# RWcircuit_1.net
KiCad netlist of a schematic drawn in Altium Designer
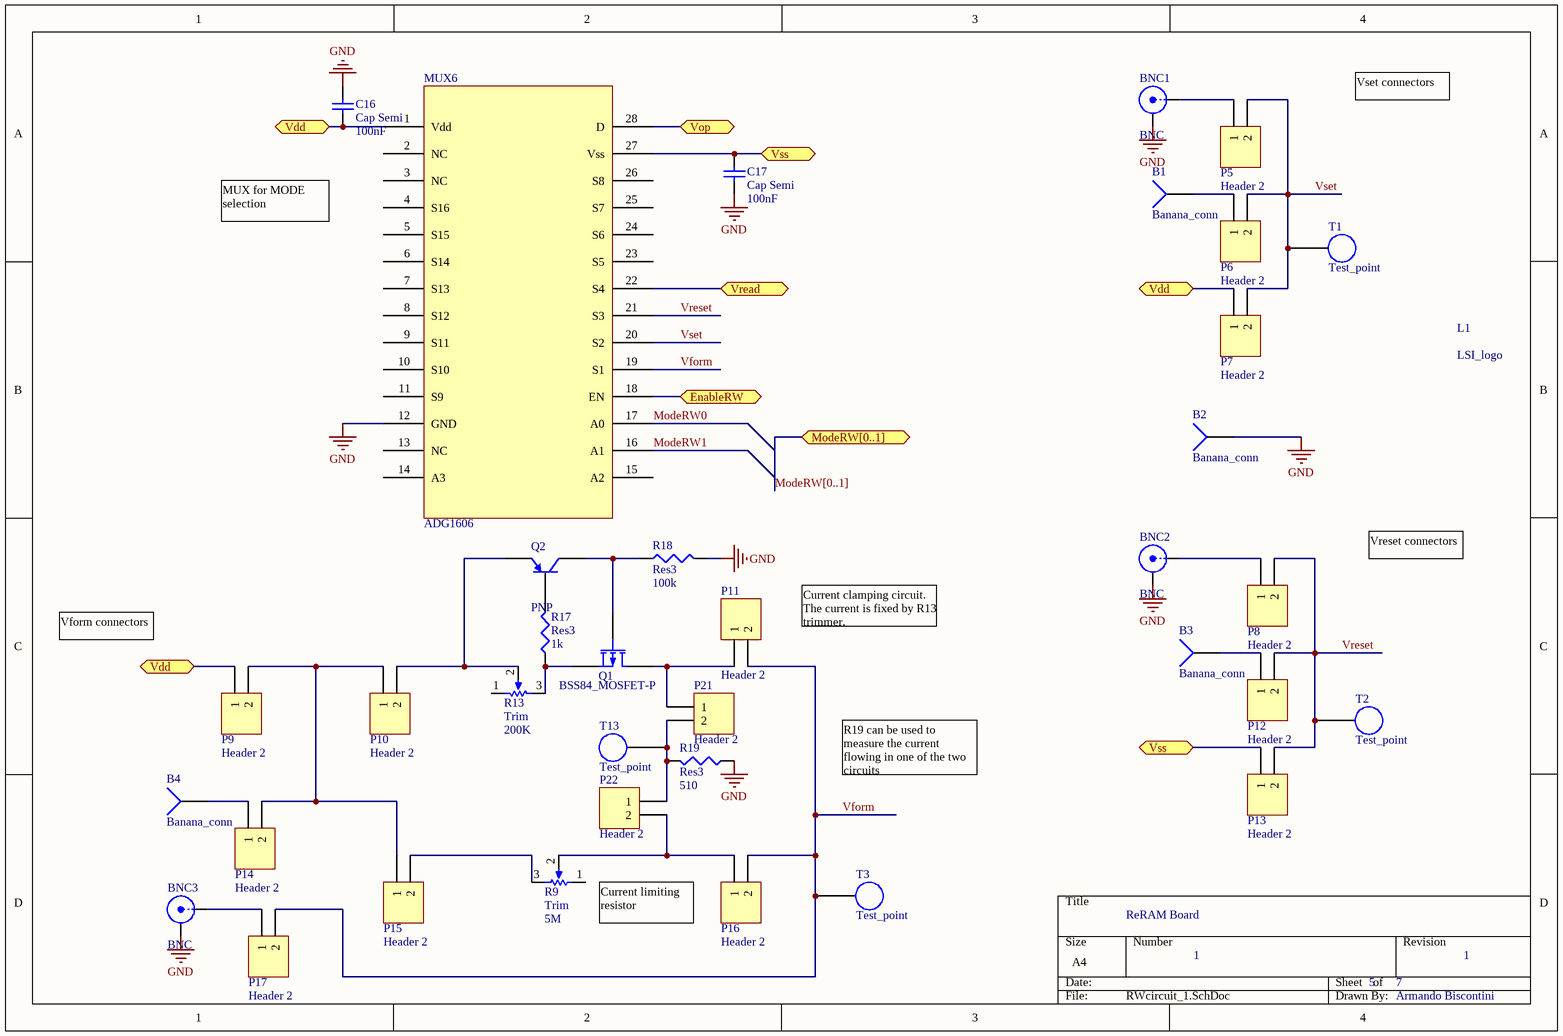
[diagram p0: RWcircuit_1.SchDoc]

(export (version "E")
  (design (tool "Eeschema 10.0.6"))
  (components
    (comp (ref "B1")
      (value "Banana_conn")
      (footprint "Banana_conn_4mm")
      (description "Multicomp banana connector 4mm pcb through hole")
      (libsource (lib "ReRAM_Board_library") (part "Banana_conn_4mm"))
    )
    (comp (ref "B2")
      (value "Banana_conn")
      (footprint "Banana_conn_4mm")
      (description "Multicomp banana connector 4mm pcb through hole")
      (libsource (lib "ReRAM_Board_library") (part "Banana_conn_4mm"))
    )
    (comp (ref "B3")
      (value "Banana_conn")
      (footprint "Banana_conn_4mm")
      (description "Multicomp banana connector 4mm pcb through hole")
      (libsource (lib "ReRAM_Board_library") (part "Banana_conn_4mm"))
    )
    (comp (ref "B4")
      (value "Banana_conn")
      (footprint "Banana_conn_4mm")
      (description "Multicomp banana connector 4mm pcb through hole")
      (libsource (lib "ReRAM_Board_library") (part "Banana_conn_4mm"))
    )
    (comp (ref "BNC1")
      (value "BNC")
      (footprint "BNC_RA CON")
      (description "BNC Elbow Connector")
      (fields (field (name "PUBLISHER") "Altium Limited"))
      (libsource (lib "Miscellaneous Connectors") (part "BNC"))
    )
    (comp (ref "BNC2")
      (value "BNC")
      (footprint "BNC_RA CON")
      (description "BNC Elbow Connector")
      (fields (field (name "PUBLISHER") "Altium Limited"))
      (libsource (lib "Miscellaneous Connectors") (part "BNC"))
    )
    (comp (ref "BNC3")
      (value "BNC")
      (footprint "BNC_RA CON")
      (description "BNC Elbow Connector")
      (fields (field (name "PUBLISHER") "Altium Limited"))
      (libsource (lib "Miscellaneous Connectors") (part "BNC"))
    )
    (comp (ref "C16")
      (value "Cap Semi")
      (footprint "C1206")
      (description "Capacitor (Semiconductor SIM Model)")
      (fields (field (name "ALTIUM_VALUE") "100nF") (field (name "PUBLISHER") "Altium Limited"))
      (libsource (lib "Miscellaneous Devices") (part "Cap Semi"))
    )
    (comp (ref "C17")
      (value "Cap Semi")
      (footprint "C1206")
      (description "Capacitor (Semiconductor SIM Model)")
      (fields (field (name "ALTIUM_VALUE") "100nF") (field (name "PUBLISHER") "Altium Limited"))
      (libsource (lib "Miscellaneous Devices") (part "Cap Semi"))
    )
    (comp (ref "L1")
      (value "LSI_logo")
      (footprint "LSI_logo")
      (description "LSI logo")
      (libsource (lib "ReRAM_Board_library") (part "LSI_logo"))
    )
    (comp (ref "MUX6")
      (value "ADG1606")
      (footprint "TSOP65P640X120-28N")
      (description "Analog Devices ADG1606")
      (libsource (lib "ReRAM_Board_library") (part "ADG1606"))
    )
    (comp (ref "P5")
      (value "Header 2")
      (footprint "HDR1X2")
      (description "Header, 2-Pin")
      (fields (field (name "PUBLISHER") "Altium Limited"))
      (libsource (lib "Miscellaneous Connectors") (part "Header 2"))
    )
    (comp (ref "P6")
      (value "Header 2")
      (footprint "HDR1X2")
      (description "Header, 2-Pin")
      (fields (field (name "PUBLISHER") "Altium Limited"))
      (libsource (lib "Miscellaneous Connectors") (part "Header 2"))
    )
    (comp (ref "P7")
      (value "Header 2")
      (footprint "HDR1X2")
      (description "Header, 2-Pin")
      (fields (field (name "PUBLISHER") "Altium Limited"))
      (libsource (lib "Miscellaneous Connectors") (part "Header 2"))
    )
    (comp (ref "P8")
      (value "Header 2")
      (footprint "HDR1X2")
      (description "Header, 2-Pin")
      (fields (field (name "PUBLISHER") "Altium Limited"))
      (libsource (lib "Miscellaneous Connectors") (part "Header 2"))
    )
    (comp (ref "P9")
      (value "Header 2")
      (footprint "HDR1X2")
      (description "Header, 2-Pin")
      (fields (field (name "PUBLISHER") "Altium Limited"))
      (libsource (lib "Miscellaneous Connectors") (part "Header 2"))
    )
    (comp (ref "P10")
      (value "Header 2")
      (footprint "HDR1X2")
      (description "Header, 2-Pin")
      (fields (field (name "PUBLISHER") "Altium Limited"))
      (libsource (lib "Miscellaneous Connectors") (part "Header 2"))
    )
    (comp (ref "P11")
      (value "Header 2")
      (footprint "HDR1X2")
      (description "Header, 2-Pin")
      (fields (field (name "PUBLISHER") "Altium Limited"))
      (libsource (lib "") (part "Header 2_2"))
    )
    (comp (ref "P12")
      (value "Header 2")
      (footprint "HDR1X2")
      (description "Header, 2-Pin")
      (fields (field (name "PUBLISHER") "Altium Limited"))
      (libsource (lib "Miscellaneous Connectors") (part "Header 2"))
    )
    (comp (ref "P13")
      (value "Header 2")
      (footprint "HDR1X2")
      (description "Header, 2-Pin")
      (fields (field (name "PUBLISHER") "Altium Limited"))
      (libsource (lib "Miscellaneous Connectors") (part "Header 2"))
    )
    (comp (ref "P14")
      (value "Header 2")
      (footprint "HDR1X2")
      (description "Header, 2-Pin")
      (fields (field (name "PUBLISHER") "Altium Limited"))
      (libsource (lib "Miscellaneous Connectors") (part "Header 2"))
    )
    (comp (ref "P15")
      (value "Header 2")
      (footprint "HDR1X2")
      (description "Header, 2-Pin")
      (fields (field (name "PUBLISHER") "Altium Limited"))
      (libsource (lib "Miscellaneous Connectors") (part "Header 2"))
    )
    (comp (ref "P16")
      (value "Header 2")
      (footprint "HDR1X2")
      (description "Header, 2-Pin")
      (fields (field (name "PUBLISHER") "Altium Limited"))
      (libsource (lib "Miscellaneous Connectors") (part "Header 2"))
    )
    (comp (ref "P17")
      (value "Header 2")
      (footprint "HDR1X2")
      (description "Header, 2-Pin")
      (fields (field (name "PUBLISHER") "Altium Limited"))
      (libsource (lib "Miscellaneous Connectors") (part "Header 2"))
    )
    (comp (ref "P21")
      (value "Header 2")
      (footprint "HDR1X2")
      (description "Header, 2-Pin")
      (fields (field (name "PUBLISHER") "Altium Limited"))
      (libsource (lib "") (part "Header 2_1"))
    )
    (comp (ref "P22")
      (value "Header 2")
      (footprint "HDR1X2")
      (description "Header, 2-Pin")
      (fields (field (name "PUBLISHER") "Altium Limited"))
      (libsource (lib "") (part "Header 2_3"))
    )
    (comp (ref "Q1")
      (value "BSS84_MOSFET-P")
      (footprint "BSS84_MOSFET-P")
      (description "BSS84 P-Channel MOSFET")
      (fields (field (name "PUBLISHER") "Altium Limited"))
      (libsource (lib "ReRAM_Board_library") (part "BSS84_MOSFET-P"))
    )
    (comp (ref "Q2")
      (value "PNP")
      (footprint "MMBT5087_PNP")
      (description "MMBT5087 PNP Bipolar Transistor")
      (fields (field (name "PUBLISHER") "Altium Limited"))
      (libsource (lib "ReRAM_Board_library") (part "MMBT5087_PNP"))
    )
    (comp (ref "R9")
      (value "Trim")
      (footprint "Trim_Bourns_3266X")
      (description "Trimmer Bourns 3266X")
      (fields (field (name "ALTIUM_VALUE") "5M") (field (name "PUBLISHER") "Altium Limited"))
      (libsource (lib "ReRAM_Board_library") (part "Trim_Bourns_3266X"))
    )
    (comp (ref "R13")
      (value "Trim")
      (footprint "Trim_Bourns_3266W")
      (description "Trimmer Bourns 3266W")
      (fields (field (name "ALTIUM_VALUE") "200K") (field (name "PUBLISHER") "Altium Limited"))
      (libsource (lib "ReRAM_Board_library") (part "Trim_Bourns_3266W"))
    )
    (comp (ref "R17")
      (value "Res3")
      (footprint "J1-0603")
      (description "Resistor")
      (fields (field (name "ALTIUM_VALUE") "1k") (field (name "PUBLISHER") "Altium Limited"))
      (libsource (lib "Miscellaneous Devices") (part "Res3"))
    )
    (comp (ref "R18")
      (value "Res3")
      (footprint "J1-0603")
      (description "Resistor")
      (fields (field (name "ALTIUM_VALUE") "100k") (field (name "PUBLISHER") "Altium Limited"))
      (libsource (lib "Miscellaneous Devices") (part "Res3"))
    )
    (comp (ref "R19")
      (value "Res3")
      (footprint "J1-0603")
      (description "Resistor")
      (fields (field (name "ALTIUM_VALUE") "510") (field (name "PUBLISHER") "Altium Limited"))
      (libsource (lib "Miscellaneous Devices") (part "Res3"))
    )
    (comp (ref "T1")
      (value "Test_point")
      (footprint "Test_point_1.32mm")
      (description "Test point 1.32mm")
      (libsource (lib "ReRAM_Board_library") (part "Test_point_1.32mm"))
    )
    (comp (ref "T2")
      (value "Test_point")
      (footprint "Test_point_1.32mm")
      (description "Test point 1.32mm")
      (libsource (lib "ReRAM_Board_library") (part "Test_point_1.32mm"))
    )
    (comp (ref "T3")
      (value "Test_point")
      (footprint "Test_point_1.32mm")
      (description "Test point 1.32mm")
      (libsource (lib "ReRAM_Board_library") (part "Test_point_1.32mm"))
    )
    (comp (ref "T13")
      (value "Test_point")
      (footprint "Test_point_1.32mm")
      (description "Test point 1.32mm")
      (libsource (lib "ReRAM_Board_library") (part "Test_point_1.32mm"))
    )
  )
  (nets
    (net (code "1") (name "/EnableRW") (class "Default")
      (node (ref "MUX6") (pin "18") (pinfunction "EN_18") (pintype "passive"))
    )
    (net (code "2") (name "/ModeRW0") (class "Default")
      (node (ref "MUX6") (pin "17") (pinfunction "A0_17") (pintype "passive"))
    )
    (net (code "3") (name "/ModeRW1") (class "Default")
      (node (ref "MUX6") (pin "16") (pinfunction "A1_16") (pintype "passive"))
    )
    (net (code "5") (name "/Vdd") (class "Default")
      (node (ref "C16") (pin "1") (pinfunction "1_1") (pintype "passive"))
      (node (ref "MUX6") (pin "1") (pinfunction "Vdd_1") (pintype "passive"))
      (node (ref "P7") (pin "1") (pinfunction "1_1") (pintype "passive"))
      (node (ref "P9") (pin "1") (pinfunction "1_1") (pintype "passive"))
    )
    (net (code "6") (name "/Vform") (class "Default")
      (node (ref "MUX6") (pin "19") (pinfunction "S1_19") (pintype "passive"))
      (node (ref "P11") (pin "2") (pinfunction "2_2") (pintype "passive"))
      (node (ref "P16") (pin "2") (pinfunction "2_2") (pintype "passive"))
      (node (ref "P17") (pin "2") (pinfunction "2_2") (pintype "passive"))
      (node (ref "T3") (pin "1") (pintype "passive"))
    )
    (net (code "7") (name "/Vop") (class "Default")
      (node (ref "MUX6") (pin "28") (pinfunction "D_28") (pintype "passive"))
    )
    (net (code "8") (name "/Vread") (class "Default")
      (node (ref "MUX6") (pin "22") (pinfunction "S4_22") (pintype "passive"))
    )
    (net (code "9") (name "/Vreset") (class "Default")
      (node (ref "MUX6") (pin "21") (pinfunction "S3_21") (pintype "passive"))
      (node (ref "P12") (pin "2") (pinfunction "2_2") (pintype "passive"))
      (node (ref "P13") (pin "2") (pinfunction "2_2") (pintype "passive"))
      (node (ref "P8") (pin "2") (pinfunction "2_2") (pintype "passive"))
      (node (ref "T2") (pin "1") (pintype "passive"))
    )
    (net (code "10") (name "/Vset") (class "Default")
      (node (ref "MUX6") (pin "20") (pinfunction "S2_20") (pintype "passive"))
      (node (ref "P5") (pin "2") (pinfunction "2_2") (pintype "passive"))
      (node (ref "P6") (pin "2") (pinfunction "2_2") (pintype "passive"))
      (node (ref "P7") (pin "2") (pinfunction "2_2") (pintype "passive"))
      (node (ref "T1") (pin "1") (pintype "passive"))
    )
    (net (code "11") (name "/Vss") (class "Default")
      (node (ref "C17") (pin "2") (pinfunction "2_2") (pintype "passive"))
      (node (ref "MUX6") (pin "27") (pinfunction "Vss_27") (pintype "passive"))
      (node (ref "P13") (pin "1") (pinfunction "1_1") (pintype "passive"))
    )
    (net (code "12") (name "GND") (class "Default")
      (node (ref "B2") (pin "1") (pinfunction "1_1") (pintype "passive"))
      (node (ref "BNC1") (pin "2") (pinfunction "Y_2") (pintype "passive"))
      (node (ref "BNC2") (pin "2") (pinfunction "Y_2") (pintype "passive"))
      (node (ref "BNC3") (pin "2") (pinfunction "Y_2") (pintype "passive"))
      (node (ref "C16") (pin "2") (pinfunction "2_2") (pintype "passive"))
      (node (ref "C17") (pin "1") (pinfunction "1_1") (pintype "passive"))
      (node (ref "MUX6") (pin "12") (pinfunction "GND_12") (pintype "passive"))
      (node (ref "R18") (pin "2") (pinfunction "2_2") (pintype "passive"))
      (node (ref "R19") (pin "1") (pinfunction "1_1") (pintype "passive"))
    )
    (net (code "13") (name "Net-(B1-Pad1)") (class "Default")
      (node (ref "B1") (pin "1") (pinfunction "1_1") (pintype "passive"))
      (node (ref "P6") (pin "1") (pinfunction "1_1") (pintype "passive"))
    )
    (net (code "14") (name "Net-(B3-Pad1)") (class "Default")
      (node (ref "B3") (pin "1") (pinfunction "1_1") (pintype "passive"))
      (node (ref "P12") (pin "1") (pinfunction "1_1") (pintype "passive"))
    )
    (net (code "15") (name "Net-(B4-Pad1)") (class "Default")
      (node (ref "B4") (pin "1") (pinfunction "1_1") (pintype "passive"))
      (node (ref "P14") (pin "1") (pinfunction "1_1") (pintype "passive"))
    )
    (net (code "16") (name "Net-(BNC1-X)") (class "Default")
      (node (ref "BNC1") (pin "1") (pinfunction "X_1") (pintype "passive"))
      (node (ref "P5") (pin "1") (pinfunction "1_1") (pintype "passive"))
    )
    (net (code "17") (name "Net-(BNC2-X)") (class "Default")
      (node (ref "BNC2") (pin "1") (pinfunction "X_1") (pintype "passive"))
      (node (ref "P8") (pin "1") (pinfunction "1_1") (pintype "passive"))
    )
    (net (code "18") (name "Net-(BNC3-X)") (class "Default")
      (node (ref "BNC3") (pin "1") (pinfunction "X_1") (pintype "passive"))
      (node (ref "P17") (pin "1") (pinfunction "1_1") (pintype "passive"))
    )
    (net (code "19") (name "Net-(P10-Pad1)") (class "Default")
      (node (ref "P10") (pin "1") (pinfunction "1_1") (pintype "passive"))
      (node (ref "P14") (pin "2") (pinfunction "2_2") (pintype "passive"))
      (node (ref "P15") (pin "1") (pinfunction "1_1") (pintype "passive"))
      (node (ref "P9") (pin "2") (pinfunction "2_2") (pintype "passive"))
    )
    (net (code "20") (name "Net-(P21-Pad2)") (class "Default")
      (node (ref "P21") (pin "2") (pinfunction "2_2") (pintype "passive"))
      (node (ref "P22") (pin "1") (pinfunction "1_1") (pintype "passive"))
      (node (ref "R19") (pin "2") (pinfunction "2_2") (pintype "passive"))
      (node (ref "T13") (pin "1") (pintype "passive"))
    )
    (net (code "21") (name "Net-(Q1-D)") (class "Default")
      (node (ref "P11") (pin "1") (pinfunction "1_1") (pintype "passive"))
      (node (ref "P21") (pin "1") (pinfunction "1_1") (pintype "passive"))
      (node (ref "Q1") (pin "3") (pinfunction "D_3") (pintype "passive"))
    )
    (net (code "22") (name "Net-(Q1-G)") (class "Default")
      (node (ref "Q1") (pin "1") (pinfunction "G_1") (pintype "passive"))
      (node (ref "Q2") (pin "1") (pinfunction "C_1") (pintype "passive"))
      (node (ref "R18") (pin "1") (pinfunction "1_1") (pintype "passive"))
    )
    (net (code "23") (name "Net-(Q1-S)") (class "Default")
      (node (ref "Q1") (pin "2") (pinfunction "S_2") (pintype "passive"))
      (node (ref "R13") (pin "3") (pinfunction "BOT_3") (pintype "passive"))
      (node (ref "R17") (pin "1") (pinfunction "1_1") (pintype "passive"))
    )
    (net (code "24") (name "Net-(Q2-B)") (class "Default")
      (node (ref "Q2") (pin "2") (pinfunction "B_2") (pintype "passive"))
      (node (ref "R17") (pin "2") (pinfunction "2_2") (pintype "passive"))
    )
    (net (code "25") (name "Net-(Q2-E)") (class "Default")
      (node (ref "P10") (pin "2") (pinfunction "2_2") (pintype "passive"))
      (node (ref "Q2") (pin "3") (pinfunction "E_3") (pintype "passive"))
      (node (ref "R13") (pin "2") (pinfunction "TAP_2") (pintype "passive"))
    )
    (net (code "26") (name "Net-(R9-BOT)") (class "Default")
      (node (ref "P15") (pin "2") (pinfunction "2_2") (pintype "passive"))
      (node (ref "R9") (pin "3") (pinfunction "BOT_3") (pintype "passive"))
    )
    (net (code "27") (name "Net-(R9-TAP)") (class "Default")
      (node (ref "P16") (pin "1") (pinfunction "1_1") (pintype "passive"))
      (node (ref "P22") (pin "2") (pinfunction "2_2") (pintype "passive"))
      (node (ref "R9") (pin "2") (pinfunction "TAP_2") (pintype "passive"))
    )
    (net (code "28") (name "unconnected-(MUX6-A2-Pad15)") (class "Default")
      (node (ref "MUX6") (pin "15") (pinfunction "A2_15") (pintype "passive"))
    )
    (net (code "29") (name "unconnected-(MUX6-A3-Pad14)") (class "Default")
      (node (ref "MUX6") (pin "14") (pinfunction "A3_14") (pintype "passive"))
    )
    (net (code "30") (name "unconnected-(MUX6-NC-Pad2)") (class "Default")
      (node (ref "MUX6") (pin "2") (pinfunction "NC_2") (pintype "passive"))
    )
    (net (code "31") (name "unconnected-(MUX6-NC-Pad3)") (class "Default")
      (node (ref "MUX6") (pin "3") (pinfunction "NC_3") (pintype "passive"))
    )
    (net (code "32") (name "unconnected-(MUX6-NC-Pad13)") (class "Default")
      (node (ref "MUX6") (pin "13") (pinfunction "NC_13") (pintype "passive"))
    )
    (net (code "33") (name "unconnected-(MUX6-S5-Pad23)") (class "Default")
      (node (ref "MUX6") (pin "23") (pinfunction "S5_23") (pintype "passive"))
    )
    (net (code "34") (name "unconnected-(MUX6-S6-Pad24)") (class "Default")
      (node (ref "MUX6") (pin "24") (pinfunction "S6_24") (pintype "passive"))
    )
    (net (code "35") (name "unconnected-(MUX6-S7-Pad25)") (class "Default")
      (node (ref "MUX6") (pin "25") (pinfunction "S7_25") (pintype "passive"))
    )
    (net (code "36") (name "unconnected-(MUX6-S8-Pad26)") (class "Default")
      (node (ref "MUX6") (pin "26") (pinfunction "S8_26") (pintype "passive"))
    )
    (net (code "37") (name "unconnected-(MUX6-S9-Pad11)") (class "Default")
      (node (ref "MUX6") (pin "11") (pinfunction "S9_11") (pintype "passive"))
    )
    (net (code "38") (name "unconnected-(MUX6-S10-Pad10)") (class "Default")
      (node (ref "MUX6") (pin "10") (pinfunction "S10_10") (pintype "passive"))
    )
    (net (code "39") (name "unconnected-(MUX6-S11-Pad9)") (class "Default")
      (node (ref "MUX6") (pin "9") (pinfunction "S11_9") (pintype "passive"))
    )
    (net (code "40") (name "unconnected-(MUX6-S12-Pad8)") (class "Default")
      (node (ref "MUX6") (pin "8") (pinfunction "S12_8") (pintype "passive"))
    )
    (net (code "41") (name "unconnected-(MUX6-S13-Pad7)") (class "Default")
      (node (ref "MUX6") (pin "7") (pinfunction "S13_7") (pintype "passive"))
    )
    (net (code "42") (name "unconnected-(MUX6-S14-Pad6)") (class "Default")
      (node (ref "MUX6") (pin "6") (pinfunction "S14_6") (pintype "passive"))
    )
    (net (code "43") (name "unconnected-(MUX6-S15-Pad5)") (class "Default")
      (node (ref "MUX6") (pin "5") (pinfunction "S15_5") (pintype "passive"))
    )
    (net (code "44") (name "unconnected-(MUX6-S16-Pad4)") (class "Default")
      (node (ref "MUX6") (pin "4") (pinfunction "S16_4") (pintype "passive"))
    )
    (net (code "45") (name "unconnected-(R9-TOP-Pad1)") (class "Default")
      (node (ref "R9") (pin "1") (pinfunction "TOP_1") (pintype "passive"))
    )
    (net (code "46") (name "unconnected-(R13-TOP-Pad1)") (class "Default")
      (node (ref "R13") (pin "1") (pinfunction "TOP_1") (pintype "passive"))
    )
  )
)
